# RGB_Matrix.net
KiCad netlist of a schematic drawn in Altium Designer
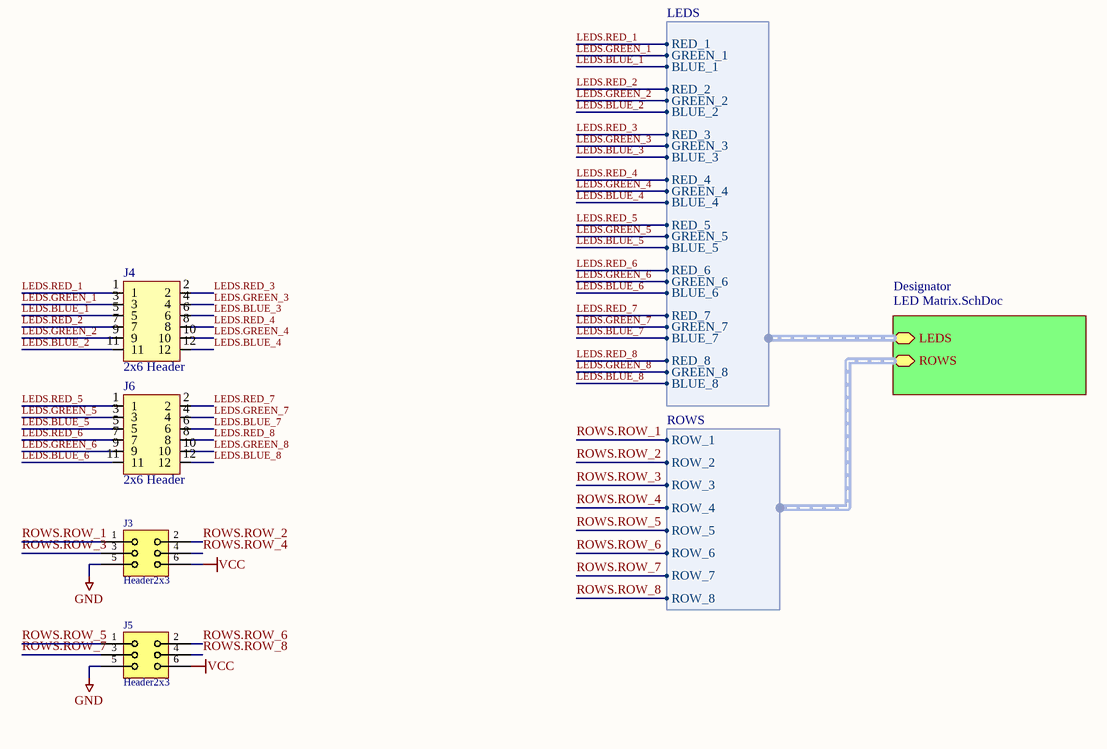
[diagram p0: RGB_Matrix.SchDoc]

(export (version "E")
  (design (tool "Eeschema 10.0.6"))
  (components
    (comp (ref "J3")
      (value "Header2x3")
      (footprint "HDRV6W64P254_2X3_762X508X900B")
      (libsource (lib "OVLib") (part "Header2x3"))
    )
    (comp (ref "J4")
      (value "2x6 Header")
      (footprint "2x6 Header")
      (libsource (lib "Schlib1") (part "2x6 Header"))
    )
    (comp (ref "J5")
      (value "Header2x3")
      (footprint "HDRV6W64P254_2X3_762X508X900B")
      (libsource (lib "OVLib") (part "Header2x3"))
    )
    (comp (ref "J6")
      (value "2x6 Header")
      (footprint "2x6 Header")
      (libsource (lib "Schlib1") (part "2x6 Header"))
    )
  )
  (nets
    (net (code "3") (name "/LEDS.BLUE_1") (class "Default")
      (node (ref "J4") (pin "5") (pinfunction "5_5") (pintype "passive"))
    )
    (net (code "4") (name "/LEDS.BLUE_2") (class "Default")
      (node (ref "J4") (pin "11") (pinfunction "11_11") (pintype "passive"))
    )
    (net (code "5") (name "/LEDS.BLUE_3") (class "Default")
      (node (ref "J4") (pin "6") (pinfunction "6_6") (pintype "passive"))
    )
    (net (code "6") (name "/LEDS.BLUE_4") (class "Default")
      (node (ref "J4") (pin "12") (pinfunction "12_12") (pintype "passive"))
    )
    (net (code "7") (name "/LEDS.BLUE_5") (class "Default")
      (node (ref "J6") (pin "5") (pinfunction "5_5") (pintype "passive"))
    )
    (net (code "8") (name "/LEDS.BLUE_6") (class "Default")
      (node (ref "J6") (pin "11") (pinfunction "11_11") (pintype "passive"))
    )
    (net (code "9") (name "/LEDS.BLUE_7") (class "Default")
      (node (ref "J6") (pin "6") (pinfunction "6_6") (pintype "passive"))
    )
    (net (code "10") (name "/LEDS.BLUE_8") (class "Default")
      (node (ref "J6") (pin "12") (pinfunction "12_12") (pintype "passive"))
    )
    (net (code "11") (name "/LEDS.GREEN_1") (class "Default")
      (node (ref "J4") (pin "3") (pinfunction "3_3") (pintype "passive"))
    )
    (net (code "12") (name "/LEDS.GREEN_2") (class "Default")
      (node (ref "J4") (pin "9") (pinfunction "9_9") (pintype "passive"))
    )
    (net (code "13") (name "/LEDS.GREEN_3") (class "Default")
      (node (ref "J4") (pin "4") (pinfunction "4_4") (pintype "passive"))
    )
    (net (code "14") (name "/LEDS.GREEN_4") (class "Default")
      (node (ref "J4") (pin "10") (pinfunction "10_10") (pintype "passive"))
    )
    (net (code "15") (name "/LEDS.GREEN_5") (class "Default")
      (node (ref "J6") (pin "3") (pinfunction "3_3") (pintype "passive"))
    )
    (net (code "16") (name "/LEDS.GREEN_6") (class "Default")
      (node (ref "J6") (pin "9") (pinfunction "9_9") (pintype "passive"))
    )
    (net (code "17") (name "/LEDS.GREEN_7") (class "Default")
      (node (ref "J6") (pin "4") (pinfunction "4_4") (pintype "passive"))
    )
    (net (code "18") (name "/LEDS.GREEN_8") (class "Default")
      (node (ref "J6") (pin "10") (pinfunction "10_10") (pintype "passive"))
    )
    (net (code "19") (name "/LEDS.RED_1") (class "Default")
      (node (ref "J4") (pin "1") (pinfunction "1_1") (pintype "passive"))
    )
    (net (code "20") (name "/LEDS.RED_2") (class "Default")
      (node (ref "J4") (pin "7") (pinfunction "7_7") (pintype "passive"))
    )
    (net (code "21") (name "/LEDS.RED_3") (class "Default")
      (node (ref "J4") (pin "2") (pinfunction "2_2") (pintype "passive"))
    )
    (net (code "22") (name "/LEDS.RED_4") (class "Default")
      (node (ref "J4") (pin "8") (pinfunction "8_8") (pintype "passive"))
    )
    (net (code "23") (name "/LEDS.RED_5") (class "Default")
      (node (ref "J6") (pin "1") (pinfunction "1_1") (pintype "passive"))
    )
    (net (code "24") (name "/LEDS.RED_6") (class "Default")
      (node (ref "J6") (pin "7") (pinfunction "7_7") (pintype "passive"))
    )
    (net (code "25") (name "/LEDS.RED_7") (class "Default")
      (node (ref "J6") (pin "2") (pinfunction "2_2") (pintype "passive"))
    )
    (net (code "26") (name "/LEDS.RED_8") (class "Default")
      (node (ref "J6") (pin "8") (pinfunction "8_8") (pintype "passive"))
    )
    (net (code "27") (name "/ROWS.ROW_1") (class "Default")
      (node (ref "J3") (pin "1") (pinfunction "1_1") (pintype "passive"))
    )
    (net (code "28") (name "/ROWS.ROW_2") (class "Default")
      (node (ref "J3") (pin "2") (pinfunction "2_2") (pintype "passive"))
    )
    (net (code "29") (name "/ROWS.ROW_3") (class "Default")
      (node (ref "J3") (pin "3") (pinfunction "3_3") (pintype "passive"))
    )
    (net (code "30") (name "/ROWS.ROW_4") (class "Default")
      (node (ref "J3") (pin "4") (pinfunction "4_4") (pintype "passive"))
    )
    (net (code "31") (name "/ROWS.ROW_5") (class "Default")
      (node (ref "J5") (pin "1") (pinfunction "1_1") (pintype "passive"))
    )
    (net (code "32") (name "/ROWS.ROW_6") (class "Default")
      (node (ref "J5") (pin "2") (pinfunction "2_2") (pintype "passive"))
    )
    (net (code "33") (name "/ROWS.ROW_7") (class "Default")
      (node (ref "J5") (pin "3") (pinfunction "3_3") (pintype "passive"))
    )
    (net (code "34") (name "/ROWS.ROW_8") (class "Default")
      (node (ref "J5") (pin "4") (pinfunction "4_4") (pintype "passive"))
    )
    (net (code "37") (name "GND") (class "Default")
      (node (ref "J3") (pin "5") (pinfunction "5_5") (pintype "passive"))
      (node (ref "J5") (pin "5") (pinfunction "5_5") (pintype "passive"))
    )
    (net (code "38") (name "VCC") (class "Default")
      (node (ref "J3") (pin "6") (pinfunction "6_6") (pintype "passive"))
      (node (ref "J5") (pin "6") (pinfunction "6_6") (pintype "passive"))
    )
  )
)
